# Sheet1.net
KiCad netlist of a schematic drawn in Altium Designer
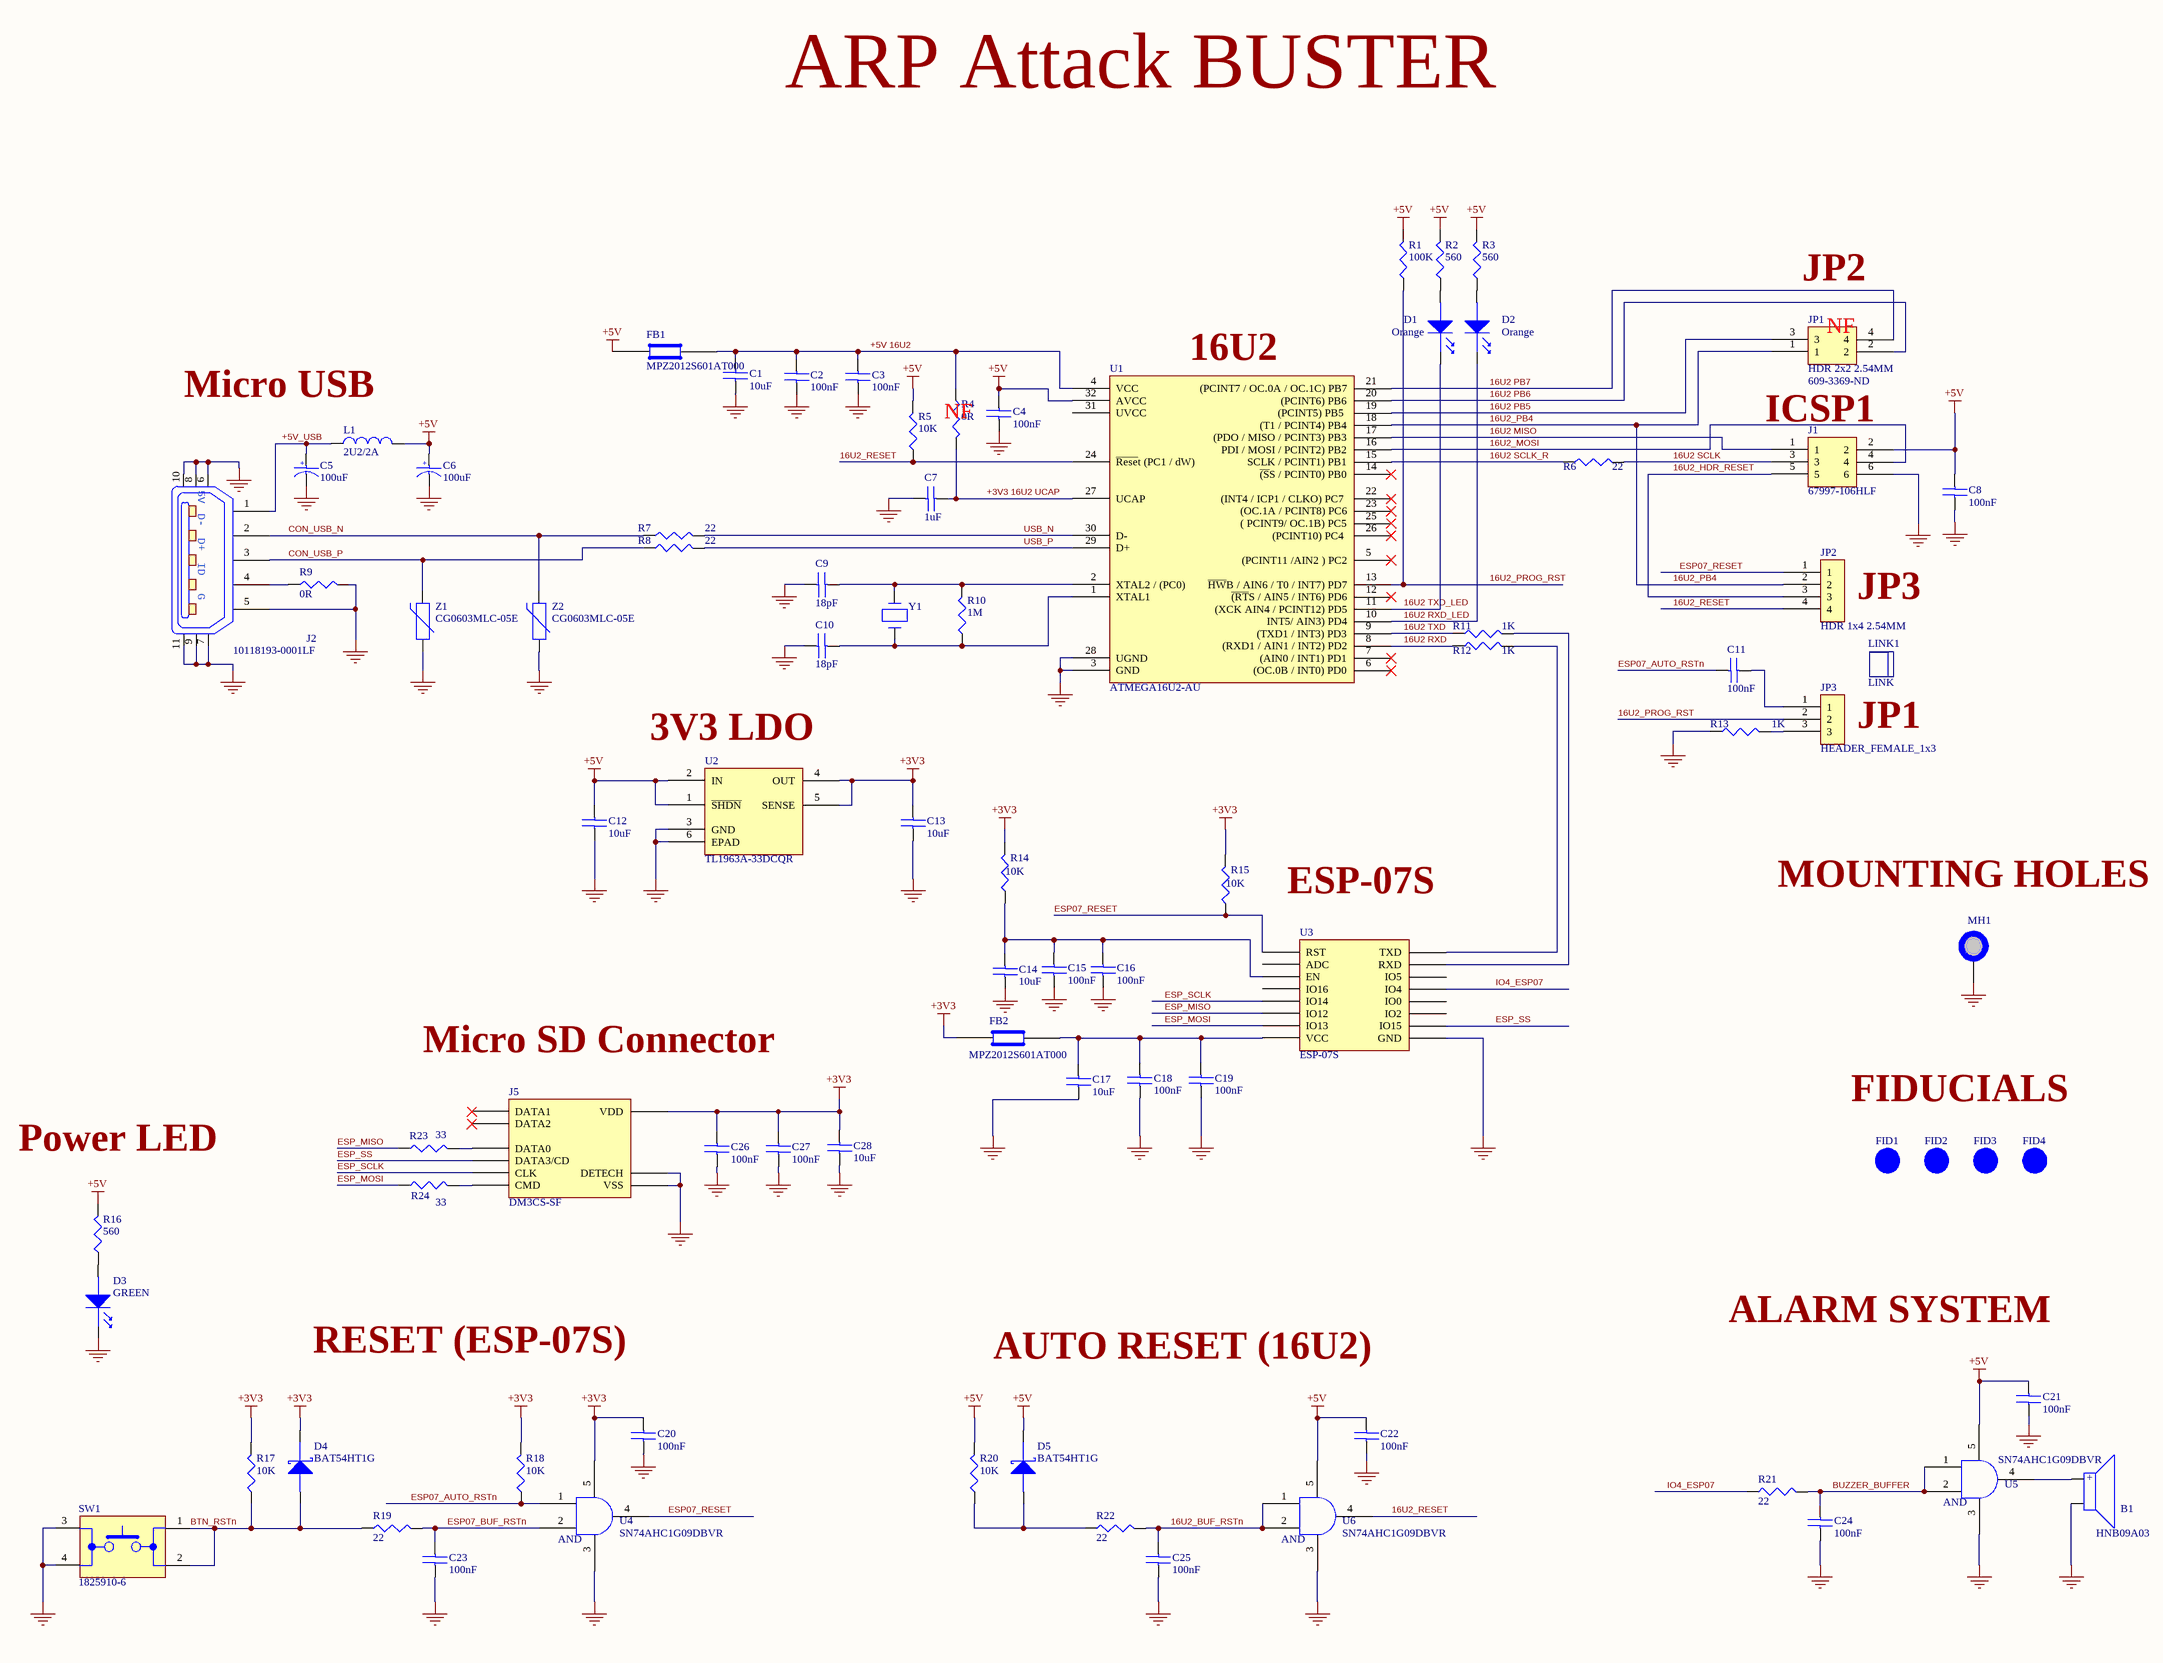
[diagram p0: Sheet1.SchDoc]

(export (version "E")
  (design (tool "Eeschema 10.0.6"))
  (components
    (comp (ref "B1")
      (value "HNB09A03")
      (footprint "Buzzer_HNB09A03")
      (description "Buzzer")
      (fields (field (name "MANUFACTURER") "Jiangsu Huaneng Elec"))
      (libsource (lib "schmaticSMDv1") (part "HNB09A03"))
    )
    (comp (ref "C1")
      (value "10uF")
      (footprint "C0805")
      (description "Cap Ceramic 10uF 10V X7S 20% Pad SMD 0805 125°C Low ESR Automotive T/R")
      (fields
        (field (name "MANUFACTURER") "TDK")
        (field (name "MANUFACTURER PART NUMBER") "CGA4J3X7S1A106M125AB")
      )
      (libsource (lib "atmega_shlib") (part "CGA4J3X7S1A106M125AB"))
    )
    (comp (ref "C2")
      (value "100nF")
      (footprint "C0805")
      (description "Cap Ceramic 0.1uF 50V X7R 10% Pad SMD 0805 125°C Automotive T/R")
      (fields
        (field (name "MANUFACTURER") "TDK")
        (field (name "MANUFACTURER PART NUMBER") "CGA4J2X7R1H104K125AM")
      )
      (libsource (lib "atmega_shlib") (part "CGA4J2X7R1H104K125AM"))
    )
    (comp (ref "C3")
      (value "100nF")
      (footprint "C0805")
      (description "Cap Ceramic 0.1uF 50V X7R 10% Pad SMD 0805 125°C Automotive T/R")
      (fields
        (field (name "MANUFACTURER") "TDK")
        (field (name "MANUFACTURER PART NUMBER") "CGA4J2X7R1H104K125AM")
      )
      (libsource (lib "atmega_shlib") (part "CGA4J2X7R1H104K125AM"))
    )
    (comp (ref "C4")
      (value "100nF")
      (footprint "C0805")
      (description "Cap Ceramic 0.1uF 50V X7R 10% Pad SMD 0805 125°C Automotive T/R")
      (fields
        (field (name "MANUFACTURER") "TDK")
        (field (name "MANUFACTURER PART NUMBER") "CGA4J2X7R1H104K125AM")
      )
      (libsource (lib "atmega_shlib") (part "CGA4J2X7R1H104K125AM"))
    )
    (comp (ref "C5")
      (value "100uF")
      (footprint "C_ALU_C_SIZE")
      (description "Cap Aluminum 100uF 10V 20% (5 X 5.4mm) SMD 50mA 1000 hr 85°C T/R")
      (fields
        (field (name "MANUFACTURER") "Panasonic")
        (field (name "MANUFACTURER PART NUMBER") "EEE-1AA101WR")
      )
      (libsource (lib "atmega_shlib") (part "EEE-1AA101WR"))
    )
    (comp (ref "C6")
      (value "100uF")
      (footprint "C_ALU_C_SIZE")
      (description "Cap Aluminum 100uF 10V 20% (5 X 5.4mm) SMD 50mA 1000 hr 85°C T/R")
      (fields
        (field (name "MANUFACTURER") "Panasonic")
        (field (name "MANUFACTURER PART NUMBER") "EEE-1AA101WR")
      )
      (libsource (lib "atmega_shlib") (part "EEE-1AA101WR"))
    )
    (comp (ref "C7")
      (value "1uF")
      (footprint "C0805")
      (fields
        (field (name "MANUFACTURER") "TDK")
        (field (name "MANUFACTURER PART NUMBER") "C2012X5R1E105K125AA")
        (field (name "TOLERANCE") "10%")
      )
      (libsource (lib "atmega_shlib") (part "C2012X5R1E105K125AA"))
    )
    (comp (ref "C8")
      (value "100nF")
      (footprint "C0805")
      (description "Cap Ceramic 0.1uF 50V X7R 10% Pad SMD 0805 125°C Automotive T/R")
      (fields
        (field (name "MANUFACTURER") "TDK")
        (field (name "MANUFACTURER PART NUMBER") "CGA4J2X7R1H104K125AM")
      )
      (libsource (lib "atmega_shlib") (part "CGA4J2X7R1H104K125AM"))
    )
    (comp (ref "C9")
      (value "18pF")
      (footprint "C0805")
      (description "Cap Ceramic 18pF 50V C0G 5% SMD 0805 125C Paper T/R")
      (fields
        (field (name "MANUFACTURER") "KEMET")
        (field (name "MANUFACTURER PART NUMBER") "C0805C180J5GACTU")
      )
      (libsource (lib "atmega_shlib") (part "C0805C180J5GACTU"))
    )
    (comp (ref "C10")
      (value "18pF")
      (footprint "C0805")
      (description "Cap Ceramic 18pF 50V C0G 5% SMD 0805 125C Paper T/R")
      (fields
        (field (name "MANUFACTURER") "KEMET")
        (field (name "MANUFACTURER PART NUMBER") "C0805C180J5GACTU")
      )
      (libsource (lib "atmega_shlib") (part "C0805C180J5GACTU"))
    )
    (comp (ref "C11")
      (value "100nF")
      (footprint "C0805")
      (description "Cap Ceramic 0.1uF 50V X7R 10% Pad SMD 0805 125°C Automotive T/R")
      (fields
        (field (name "MANUFACTURER") "TDK")
        (field (name "MANUFACTURER PART NUMBER") "CGA4J2X7R1H104K125AM")
      )
      (libsource (lib "atmega_shlib") (part "CGA4J2X7R1H104K125AM"))
    )
    (comp (ref "C12")
      (value "10uF")
      (footprint "C0805")
      (description "Cap Ceramic 10uF 10V X7S 20% Pad SMD 0805 125°C Low ESR Automotive T/R")
      (fields
        (field (name "MANUFACTURER") "TDK")
        (field (name "MANUFACTURER PART NUMBER") "CGA4J3X7S1A106M125AB")
      )
      (libsource (lib "atmega_shlib") (part "CGA4J3X7S1A106M125AB"))
    )
    (comp (ref "C13")
      (value "10uF")
      (footprint "C0805")
      (description "Cap Ceramic 10uF 10V X7S 20% Pad SMD 0805 125°C Low ESR Automotive T/R")
      (fields
        (field (name "MANUFACTURER") "TDK")
        (field (name "MANUFACTURER PART NUMBER") "CGA4J3X7S1A106M125AB")
      )
      (libsource (lib "atmega_shlib") (part "CGA4J3X7S1A106M125AB"))
    )
    (comp (ref "C14")
      (value "10uF")
      (footprint "C0805")
      (description "Cap Ceramic 10uF 10V X7S 20% Pad SMD 0805 125°C Low ESR Automotive T/R")
      (fields
        (field (name "MANUFACTURER") "TDK")
        (field (name "MANUFACTURER PART NUMBER") "CGA4J3X7S1A106M125AB")
      )
      (libsource (lib "schmaticSMDv1") (part "CGA4J3X7S1A106M125AB"))
    )
    (comp (ref "C15")
      (value "100nF")
      (footprint "C0805")
      (description "Cap Ceramic 0.1uF 50V X7R 10% Pad SMD 0805 125°C Automotive T/R")
      (fields
        (field (name "MANUFACTURER") "TDK")
        (field (name "MANUFACTURER PART NUMBER") "CGA4J2X7R1H104K125AM")
      )
      (libsource (lib "schmaticSMDv1") (part "CGA4J2X7R1H104K125AM"))
    )
    (comp (ref "C16")
      (value "100nF")
      (footprint "C0805")
      (description "Cap Ceramic 0.1uF 50V X7R 10% Pad SMD 0805 125°C Automotive T/R")
      (fields
        (field (name "MANUFACTURER") "TDK")
        (field (name "MANUFACTURER PART NUMBER") "CGA4J2X7R1H104K125AM")
      )
      (libsource (lib "schmaticSMDv1") (part "CGA4J2X7R1H104K125AM"))
    )
    (comp (ref "C17")
      (value "10uF")
      (footprint "C0805")
      (description "Cap Ceramic 10uF 10V X7S 20% Pad SMD 0805 125°C Low ESR Automotive T/R")
      (fields
        (field (name "MANUFACTURER") "TDK")
        (field (name "MANUFACTURER PART NUMBER") "CGA4J3X7S1A106M125AB")
      )
      (libsource (lib "schmaticSMDv1") (part "CGA4J3X7S1A106M125AB"))
    )
    (comp (ref "C18")
      (value "100nF")
      (footprint "C0805")
      (description "Cap Ceramic 0.1uF 50V X7R 10% Pad SMD 0805 125°C Automotive T/R")
      (fields
        (field (name "MANUFACTURER") "TDK")
        (field (name "MANUFACTURER PART NUMBER") "CGA4J2X7R1H104K125AM")
      )
      (libsource (lib "schmaticSMDv1") (part "CGA4J2X7R1H104K125AM"))
    )
    (comp (ref "C19")
      (value "100nF")
      (footprint "C0805")
      (description "Cap Ceramic 0.1uF 50V X7R 10% Pad SMD 0805 125°C Automotive T/R")
      (fields
        (field (name "MANUFACTURER") "TDK")
        (field (name "MANUFACTURER PART NUMBER") "CGA4J2X7R1H104K125AM")
      )
      (libsource (lib "schmaticSMDv1") (part "CGA4J2X7R1H104K125AM"))
    )
    (comp (ref "C20")
      (value "100nF")
      (footprint "C0805")
      (description "Cap Ceramic 0.1uF 50V X7R 10% Pad SMD 0805 125°C Automotive T/R")
      (fields
        (field (name "MANUFACTURER") "TDK")
        (field (name "MANUFACTURER PART NUMBER") "CGA4J2X7R1H104K125AM")
      )
      (libsource (lib "atmega_shlib") (part "CGA4J2X7R1H104K125AM"))
    )
    (comp (ref "C21")
      (value "100nF")
      (footprint "C0805")
      (description "Cap Ceramic 0.1uF 50V X7R 10% Pad SMD 0805 125°C Automotive T/R")
      (fields
        (field (name "MANUFACTURER") "TDK")
        (field (name "MANUFACTURER PART NUMBER") "CGA4J2X7R1H104K125AM")
      )
      (libsource (lib "atmega_shlib") (part "CGA4J2X7R1H104K125AM"))
    )
    (comp (ref "C22")
      (value "100nF")
      (footprint "C0805")
      (description "Cap Ceramic 0.1uF 50V X7R 10% Pad SMD 0805 125°C Automotive T/R")
      (fields
        (field (name "MANUFACTURER") "TDK")
        (field (name "MANUFACTURER PART NUMBER") "CGA4J2X7R1H104K125AM")
      )
      (libsource (lib "atmega_shlib") (part "CGA4J2X7R1H104K125AM"))
    )
    (comp (ref "C23")
      (value "100nF")
      (footprint "C0805")
      (description "Cap Ceramic 0.1uF 50V X7R 10% Pad SMD 0805 125°C Automotive T/R")
      (fields
        (field (name "MANUFACTURER") "TDK")
        (field (name "MANUFACTURER PART NUMBER") "CGA4J2X7R1H104K125AM")
      )
      (libsource (lib "atmega_shlib") (part "CGA4J2X7R1H104K125AM"))
    )
    (comp (ref "C24")
      (value "100nF")
      (footprint "C0805")
      (description "Cap Ceramic 0.1uF 50V X7R 10% Pad SMD 0805 125°C Automotive T/R")
      (fields
        (field (name "MANUFACTURER") "TDK")
        (field (name "MANUFACTURER PART NUMBER") "CGA4J2X7R1H104K125AM")
      )
      (libsource (lib "atmega_shlib") (part "CGA4J2X7R1H104K125AM"))
    )
    (comp (ref "C25")
      (value "100nF")
      (footprint "C0805")
      (description "Cap Ceramic 0.1uF 50V X7R 10% Pad SMD 0805 125°C Automotive T/R")
      (fields
        (field (name "MANUFACTURER") "TDK")
        (field (name "MANUFACTURER PART NUMBER") "CGA4J2X7R1H104K125AM")
      )
      (libsource (lib "atmega_shlib") (part "CGA4J2X7R1H104K125AM"))
    )
    (comp (ref "C26")
      (value "100nF")
      (footprint "C0805")
      (description "Cap Ceramic 0.1uF 50V X7R 10% Pad SMD 0805 125°C Automotive T/R")
      (fields
        (field (name "MANUFACTURER") "TDK")
        (field (name "MANUFACTURER PART NUMBER") "CGA4J2X7R1H104K125AM")
      )
      (libsource (lib "atmega_shlib") (part "CGA4J2X7R1H104K125AM"))
    )
    (comp (ref "C27")
      (value "100nF")
      (footprint "C0805")
      (description "Cap Ceramic 0.1uF 50V X7R 10% Pad SMD 0805 125°C Automotive T/R")
      (fields
        (field (name "MANUFACTURER") "TDK")
        (field (name "MANUFACTURER PART NUMBER") "CGA4J2X7R1H104K125AM")
      )
      (libsource (lib "atmega_shlib") (part "CGA4J2X7R1H104K125AM"))
    )
    (comp (ref "C28")
      (value "10uF")
      (footprint "C0805")
      (description "Cap Ceramic 10uF 10V X7S 20% Pad SMD 0805 125°C Low ESR Automotive T/R")
      (fields
        (field (name "MANUFACTURER") "TDK")
        (field (name "MANUFACTURER PART NUMBER") "CGA4J3X7S1A106M125AB")
      )
      (libsource (lib "atmega_shlib") (part "CGA4J3X7S1A106M125AB"))
    )
    (comp (ref "D1")
      (value "Orange")
      (footprint "LED0603")
      (description "Smartled Orange Lc")
      (fields
        (field (name "MANUFACTURER") "Osram Opto")
        (field (name "MANUFACTURER PART NUMBER") "LOL29K-H2K1-24-Z")
      )
      (libsource (lib "atmega_shlib") (part "LOL29K-H2K1-24-Z"))
    )
    (comp (ref "D2")
      (value "Orange")
      (footprint "LED0603")
      (description "Smartled Orange Lc")
      (fields
        (field (name "MANUFACTURER") "Osram Opto")
        (field (name "MANUFACTURER PART NUMBER") "LOL29K-H2K1-24-Z")
      )
      (libsource (lib "atmega_shlib") (part "LOL29K-H2K1-24-Z"))
    )
    (comp (ref "D3")
      (value "GREEN")
      (footprint "LED0603")
      (description "LED Single Chip Green 570nm 20mA 2-Pin 0603 T/R")
      (fields
        (field (name "MANUFACTURER") "Osram Opto")
        (field (name "MANUFACTURER PART NUMBER") "LGL29K-G2J1-24-Z")
      )
      (libsource (lib "atmega_shlib") (part "LGL29K-G2J1-24-Z"))
    )
    (comp (ref "D4")
      (value "BAT54HT1G")
      (footprint "SOD323")
      (description "Small Signal Schottky Diode, Single, 30 V, 200 Ma, 800 Mv, 600 Ma, 150 C")
      (fields (field (name "MANUFACTURER") "ON Semiconductor / Fairchild"))
      (libsource (lib "atmega_shlib") (part "BAT54HT1G"))
    )
    (comp (ref "D5")
      (value "BAT54HT1G")
      (footprint "SOD323")
      (description "Small Signal Schottky Diode, Single, 30 V, 200 Ma, 800 Mv, 600 Ma, 150 C")
      (fields (field (name "MANUFACTURER") "ON Semiconductor / Fairchild"))
      (libsource (lib "atmega_shlib") (part "BAT54HT1G"))
    )
    (comp (ref "FB1")
      (value "MPZ2012S601AT000")
      (footprint "C0805")
      (description "Ferrite Beads Multi-Layer Power 600Ohm 25% 100MHz 2A 100mOhm DCR 0805 T/R")
      (fields (field (name "MANUFACTURER") "TDK"))
      (libsource (lib "atmega_shlib") (part "MPZ2012S601AT000"))
    )
    (comp (ref "FB2")
      (value "MPZ2012S601AT000")
      (footprint "C0805")
      (description "Ferrite Beads Multi-Layer Power 600Ohm 25% 100MHz 2A 100mOhm DCR 0805 T/R")
      (fields (field (name "MANUFACTURER") "TDK"))
      (libsource (lib "atmega_shlib") (part "MPZ2012S601AT000"))
    )
    (comp (ref "FID1")
      (value "FID_1MM")
      (footprint "FID_x_420")
      (description "Fisushal 1MM")
      (libsource (lib "atmega_shlib") (part "FID_1MM"))
    )
    (comp (ref "FID2")
      (value "FID_1MM")
      (footprint "FID_x_420")
      (description "Fisushal 1MM")
      (libsource (lib "atmega_shlib") (part "FID_1MM"))
    )
    (comp (ref "FID3")
      (value "FID_1MM")
      (footprint "FID_x_420")
      (description "Fisushal 1MM")
      (libsource (lib "atmega_shlib") (part "FID_1MM"))
    )
    (comp (ref "FID4")
      (value "FID_1MM")
      (footprint "FID_x_420")
      (description "Fisushal 1MM")
      (libsource (lib "atmega_shlib") (part "FID_1MM"))
    )
    (comp (ref "J1")
      (value "67997-106HLF")
      (footprint "HDR_2x3_2.54MM")
      (description "Conn Unshrouded Header HDR 6 POS 2.54mm Solder ST Top Entry Thru-Hole BergStik® Bulk")
      (fields (field (name "MANUFACTURER") "ICC"))
      (libsource (lib "atmega_shlib") (part "67997-106HLF"))
    )
    (comp (ref "J2")
      (value "10118193-0001LF")
      (footprint "10118193-0001LF")
      (description "FCI Right Angle Surface Mount Mount Female USB Connector; 100 V ac; 1.8A")
      (fields (field (name "MANUFACTURER") "Amphenol ICC / FCI"))
      (libsource (lib "atmega_shlib") (part "10118193-0001LF"))
    )
    (comp (ref "J5")
      (value "DM3CS-SF")
      (footprint "GCT_MEM2051-00-195-00-A")
      (description "Connector, Memory, Micro Sd, Hinged Rohs Compliant: Yes")
      (fields (field (name "MANUFACTURER") "Hirose"))
      (libsource (lib "schmaticSMDv1") (part "DM3CS-SF"))
    )
    (comp (ref "JP1")
      (value "HDR 2x2 2.54MM")
      (footprint "HDR_2x2_2.54MM")
      (description "Conn Unshrouded Header HDR 4 POS 2.54mm Solder ST Top Entry Thru-Hole BergStik® Bulk")
      (fields
        (field (name "MANUFACTURER") "Amphenol ICC / FCI")
        (field (name "MANUFACTURER PART NUMBER") "68602-204HLF")
        (field (name "SUPPLIER PART NUMBER 1") "609-3369-ND")
      )
      (libsource (lib "atmega_shlib") (part "68602-204HLF"))
    )
    (comp (ref "JP2")
      (value "HDR 1x4 2.54MM")
      (footprint "MALEHEADER_1x4_2.54MM")
      (description "Conn Unshrouded Header HDR 4 POS 2.54mm Solder ST Thru-Hole Bag")
      (fields
        (field (name "MANUFACTURER") "Amphenol ICC / FCI")
        (field (name "MANUFACTURER PART NUMBER") "68001-204HLF")
      )
      (libsource (lib "atmega_shlib") (part "68001-204HLF"))
    )
    (comp (ref "JP3")
      (value "HEADER_FEMALE_1x3")
      (footprint "HDR_1x3_2.54MM")
      (description "Conn Unshrouded Header HDR 3 POS 2.54mm Solder ST Top Entry Thru-Hole BergStik® Automotive Bulk")
      (fields
        (field (name "MANUFACTURER") "Amphenol ICC")
        (field (name "MANUFACTURER PART NUMBER") "68000-103HLF")
      )
      (libsource (lib "atmega_shlib") (part "68000-103HLF"))
    )
    (comp (ref "L1")
      (value "2U2/2A")
      (footprint "CL_inductor")
      (description "Inductor RF Chip Wirewound 2.2uH 20% 100KHz 1.13A 0.104Ohm DCR 1210 T/R")
      (fields
        (field (name "MANUFACTURER") "KEMET")
        (field (name "MANUFACTURER PART NUMBER") "L1210R2R2MDWIT")
      )
      (libsource (lib "atmega_shlib") (part "L1210R2R2MDWIT"))
    )
    (comp (ref "LINK1")
      (value "LINK")
      (description "2 Position 2.54 mm Centerline Single Circuit Open Top Jumper")
      (fields
        (field (name "MANUFACTURER") "Sullins")
        (field (name "MANUFACTURER PART NUMBER") "QPC02SXGN-RC")
      )
      (libsource (lib "atmega_shlib") (part "QPC02SXGN-RC"))
    )
    (comp (ref "MH1")
      (value "Mounting_hole_17.4_3.2")
      (footprint "MH_17.4_3.2")
      (description "Mounting Hole plated")
      (libsource (lib "atmega_shlib") (part "Mounting_hole_17.4_3.2"))
    )
    (comp (ref "R1")
      (value "100K")
      (footprint "R0805")
      (description "Res Thick Film 0805 100K Ohm 1% 1/8W ±100ppm/°C Molded SMD Paper T/R")
      (fields
        (field (name "MANUFACTURER") "Yageo")
        (field (name "MANUFACTURER PART NUMBER") "RC0805FR-07100KL")
      )
      (libsource (lib "atmega_shlib") (part "RC0805FR-07100KL"))
    )
    (comp (ref "R2")
      (value "560")
      (footprint "R0805")
      (description "Res General Purpose Thick Film 0805 560 Ohm 1% 1/8W ±100ppm/°C Molded Paper T/R")
      (fields
        (field (name "MANUFACTURER") "Yageo")
        (field (name "MANUFACTURER PART NUMBER") "RC0805FR-07560RL")
      )
      (libsource (lib "atmega_shlib") (part "RC0805FR-07560RL"))
    )
    (comp (ref "R3")
      (value "560")
      (footprint "R0805")
      (description "Res General Purpose Thick Film 0805 560 Ohm 1% 1/8W ±100ppm/°C Molded Paper T/R")
      (fields
        (field (name "MANUFACTURER") "Yageo")
        (field (name "MANUFACTURER PART NUMBER") "RC0805FR-07560RL")
      )
      (libsource (lib "atmega_shlib") (part "RC0805FR-07560RL"))
    )
    (comp (ref "R4")
      (value "0R")
      (footprint "R0805")
      (description "RC Series 0805 0.125 W 0 Ohm Jumper Surface Mount Thick Film Chip Resistor")
      (fields
        (field (name "MANUFACTURER") "Yageo")
        (field (name "MANUFACTURER PART NUMBER") "RC0805JR-070RL")
      )
      (libsource (lib "atmega_shlib") (part "RC0805JR-070RL"))
    )
    (comp (ref "R5")
      (value "10K")
      (footprint "R0805")
      (description "Res SMD 0805 10K 1% 0.125W T.C.100PPM")
      (fields
        (field (name "MANUFACTURER") "Yageo")
        (field (name "MANUFACTURER PART NUMBER") "RC0805FR-0710KL")
      )
      (libsource (lib "atmega_shlib") (part "RC0805FR-0710KL"))
    )
    (comp (ref "R6")
      (value "22")
      (footprint "R0805")
      (description "Res SMD 0805 22R 1% 0.125W T.C.100PPM")
      (fields
        (field (name "MANUFACTURER") "Yageo")
        (field (name "MANUFACTURER PART NUMBER") "RC0805FR-0722RL")
      )
      (libsource (lib "atmega_shlib") (part "RC0805FR-0722RL"))
    )
    (comp (ref "R7")
      (value "22")
      (footprint "R0805")
      (description "Res SMD 0805 22R 1% 0.125W T.C.100PPM")
      (fields
        (field (name "MANUFACTURER") "Yageo")
        (field (name "MANUFACTURER PART NUMBER") "RC0805FR-0722RL")
      )
      (libsource (lib "atmega_shlib") (part "RC0805FR-0722RL"))
    )
    (comp (ref "R8")
      (value "22")
      (footprint "R0805")
      (description "Res SMD 0805 22R 1% 0.125W T.C.100PPM")
      (fields
        (field (name "MANUFACTURER") "Yageo")
        (field (name "MANUFACTURER PART NUMBER") "RC0805FR-0722RL")
      )
      (libsource (lib "atmega_shlib") (part "RC0805FR-0722RL"))
    )
    (comp (ref "R9")
      (value "0R")
      (footprint "R0805")
      (description "RC Series 0805 0.125 W 0 Ohm Jumper Surface Mount Thick Film Chip Resistor")
      (fields
        (field (name "MANUFACTURER") "Yageo")
        (field (name "MANUFACTURER PART NUMBER") "RC0805JR-070RL")
      )
      (libsource (lib "atmega_shlib") (part "RC0805JR-070RL"))
    )
    (comp (ref "R10")
      (value "1M")
      (footprint "R0805")
      (description "Res Thick Film 0805 1M Ohm 1% 0.125W(1/8W) ±100ppm/C Pad SMD T/R")
      (fields
        (field (name "MANUFACTURER") "Yageo Phycomp")
        (field (name "MANUFACTURER PART NUMBER") "RC0805FR-071ML")
      )
      (libsource (lib "atmega_shlib") (part "RC0805FR-071ML"))
    )
    (comp (ref "R11")
      (value "1K")
      (footprint "R0805")
      (description "Res Thick Film 0805 1KOhm 1% 0.125W(1/8W) 100ppm/C Epoxy Pad SMD T/R")
      (fields
        (field (name "MANUFACTURER") "Yageo")
        (field (name "MANUFACTURER PART NUMBER") "RC0805FR-071KL")
      )
      (libsource (lib "atmega_shlib") (part "RC0805FR-071KL"))
    )
    (comp (ref "R12")
      (value "1K")
      (footprint "R0805")
      (description "Res Thick Film 0805 1KOhm 1% 0.125W(1/8W) 100ppm/C Epoxy Pad SMD T/R")
      (fields
        (field (name "MANUFACTURER") "Yageo")
        (field (name "MANUFACTURER PART NUMBER") "RC0805FR-071KL")
      )
      (libsource (lib "atmega_shlib") (part "RC0805FR-071KL"))
    )
    (comp (ref "R13")
      (value "1K")
      (footprint "R0805")
      (description "Res Thick Film 0805 1KOhm 1% 0.125W(1/8W) 100ppm/C Epoxy Pad SMD T/R")
      (fields
        (field (name "MANUFACTURER") "Yageo")
        (field (name "MANUFACTURER PART NUMBER") "RC0805FR-071KL")
      )
      (libsource (lib "atmega_shlib") (part "RC0805FR-071KL"))
    )
    (comp (ref "R14")
      (value "10K")
      (footprint "R0805")
      (description "Res SMD 0805 10K 1% 0.125W T.C.100PPM")
      (fields
        (field (name "MANUFACTURER") "Yageo")
        (field (name "MANUFACTURER PART NUMBER") "RC0805FR-0710KL")
      )
      (libsource (lib "atmega_shlib") (part "RC0805FR-0710KL"))
    )
    (comp (ref "R15")
      (value "10K")
      (footprint "R0805")
      (description "Res SMD 0805 10K 1% 0.125W T.C.100PPM")
      (fields
        (field (name "MANUFACTURER") "Yageo")
        (field (name "MANUFACTURER PART NUMBER") "RC0805FR-0710KL")
      )
      (libsource (lib "atmega_shlib") (part "RC0805FR-0710KL"))
    )
    (comp (ref "R16")
      (value "560")
      (footprint "R0805")
      (description "Res General Purpose Thick Film 0805 560 Ohm 1% 1/8W ±100ppm/°C Molded Paper T/R")
      (fields
        (field (name "MANUFACTURER") "Yageo")
        (field (name "MANUFACTURER PART NUMBER") "RC0805FR-07560RL")
      )
      (libsource (lib "atmega_shlib") (part "RC0805FR-07560RL"))
    )
    (comp (ref "R17")
      (value "10K")
      (footprint "R0805")
      (description "Res SMD 0805 10K 1% 0.125W T.C.100PPM")
      (fields
        (field (name "MANUFACTURER") "Yageo")
        (field (name "MANUFACTURER PART NUMBER") "RC0805FR-0710KL")
      )
      (libsource (lib "atmega_shlib") (part "RC0805FR-0710KL"))
    )
    (comp (ref "R18")
      (value "10K")
      (footprint "R0805")
      (description "Res SMD 0805 10K 1% 0.125W T.C.100PPM")
      (fields
        (field (name "MANUFACTURER") "Yageo")
        (field (name "MANUFACTURER PART NUMBER") "RC0805FR-0710KL")
      )
      (libsource (lib "atmega_shlib") (part "RC0805FR-0710KL"))
    )
    (comp (ref "R19")
      (value "22")
      (footprint "R0805")
      (description "Res SMD 0805 22R 1% 0.125W T.C.100PPM")
      (fields
        (field (name "MANUFACTURER") "Yageo")
        (field (name "MANUFACTURER PART NUMBER") "RC0805FR-0722RL")
      )
      (libsource (lib "atmega_shlib") (part "RC0805FR-0722RL"))
    )
    (comp (ref "R20")
      (value "10K")
      (footprint "R0805")
      (description "Res SMD 0805 10K 1% 0.125W T.C.100PPM")
      (fields
        (field (name "MANUFACTURER") "Yageo")
        (field (name "MANUFACTURER PART NUMBER") "RC0805FR-0710KL")
      )
      (libsource (lib "atmega_shlib") (part "RC0805FR-0710KL"))
    )
    (comp (ref "R21")
      (value "22")
      (footprint "R0805")
      (description "Res SMD 0805 22R 1% 0.125W T.C.100PPM")
      (fields
        (field (name "MANUFACTURER") "Yageo")
        (field (name "MANUFACTURER PART NUMBER") "RC0805FR-0722RL")
      )
      (libsource (lib "atmega_shlib") (part "RC0805FR-0722RL"))
    )
    (comp (ref "R22")
      (value "22")
      (footprint "R0805")
      (description "Res SMD 0805 22R 1% 0.125W T.C.100PPM")
      (fields
        (field (name "MANUFACTURER") "Yageo")
        (field (name "MANUFACTURER PART NUMBER") "RC0805FR-0722RL")
      )
      (libsource (lib "atmega_shlib") (part "RC0805FR-0722RL"))
    )
    (comp (ref "R23")
      (value "33")
      (footprint "R0805")
      (description "Res Thick Film 2010 33 Ohm 1% 1W ±100ppm/C Pad SMD Automotive T/R")
      (fields
        (field (name "MANUFACTURER") "Stackpole Electronics")
        (field (name "MANUFACTURER PART NUMBER") "RMCP2010FT33R0")
      )
      (libsource (lib "schmaticSMDv1") (part "RMCP2010FT33R0"))
    )
    (comp (ref "R24")
      (value "33")
      (footprint "R0805")
      (description "Res Thick Film 2010 33 Ohm 1% 1W ±100ppm/C Pad SMD Automotive T/R")
      (fields
        (field (name "MANUFACTURER") "Stackpole Electronics")
        (field (name "MANUFACTURER PART NUMBER") "RMCP2010FT33R0")
      )
      (libsource (lib "schmaticSMDv1") (part "RMCP2010FT33R0"))
    )
    (comp (ref "SW1")
      (value "1825910-6")
      (footprint "DIP41825910-6")
      (description "Switch Tactile OFF (ON) SPST Round Button PC Pins 0.05A 24VDC 1.57N Thru-Hole Loose")
      (fields (field (name "MANUFACTURER") "TE Connectivity Alcoswitch"))
      (libsource (lib "atmega_shlib") (part "1825910-6"))
    )
    (comp (ref "U1")
      (value "ATMEGA16U2-AU")
      (footprint "TQFP_32")
      (description "8-bit AVR MCU, 16 KB, 512 Bytes, 16 MHz, 2.7 to 5.5V, TQFP-32, RoHS")
      (fields (field (name "MANUFACTURER") "Microchip / Atmel"))
      (libsource (lib "atmega_shlib") (part "ATMEGA16U2-AU"))
    )
    (comp (ref "U2")
      (value "TL1963A-33DCQR")
      (footprint "TL1963A-33DCQR")
      (description "LDO Regulator Pos 3.3V 1.5A 6-Pin(5+Tab) SOT-223 T/R")
      (fields (field (name "MANUFACTURER") "Texas Instruments"))
      (libsource (lib "atmega_shlib") (part "TL1963A-33DCQR"))
    )
    (comp (ref "U3")
      (value "ESP-07S")
      (footprint "ESP-07S")
      (description "Wifi Module, 2.484Ghz, 9 I/o Port Rohs Compliant: Yes")
      (fields
        (field (name "MANUFACTURER") "RF Solutions")
        (field (name "MANUFACTURER PART NUMBER") "ESP-12S")
      )
      (libsource (lib "schmaticSMDv1") (part "ESP-07S"))
    )
    (comp (ref "U4")
      (value "SN74AHC1G09DBVR")
      (footprint "DBV_SOT_5")
      (description "Single 2-input, 2-V to 5.5-V AND gate with open-drain outputs 5-SOT-23 -55 to 125")
      (fields (field (name "MANUFACTURER") "Texas Instruments"))
      (libsource (lib "atmega_shlib") (part "SN74AHC1G09DBVR"))
    )
    (comp (ref "U5")
      (value "SN74AHC1G09DBVR")
      (footprint "DBV_SOT_5")
      (description "Single 2-input, 2-V to 5.5-V AND gate with open-drain outputs 5-SOT-23 -55 to 125")
      (fields (field (name "MANUFACTURER") "Texas Instruments"))
      (libsource (lib "atmega_shlib") (part "SN74AHC1G09DBVR"))
    )
    (comp (ref "U6")
      (value "SN74AHC1G09DBVR")
      (footprint "DBV_SOT_5")
      (description "Single 2-input, 2-V to 5.5-V AND gate with open-drain outputs 5-SOT-23 -55 to 125")
      (fields (field (name "MANUFACTURER") "Texas Instruments"))
      (libsource (lib "atmega_shlib") (part "SN74AHC1G09DBVR"))
    )
    (comp (ref "Y1")
      (value "ABM7-16.000MHZ-D2Y-T")
      (footprint "ABM4_v1_1_BIG")
      (description "Crystal 16MHz ±20ppm (Tol) ±30ppm (Stability) 18pF FUND 50Ohm 2-Pin Mini-CSMD T/R")
      (fields (field (name "MANUFACTURER") "Abracon") (field (name "TOLERANCE") "20ppm"))
      (libsource (lib "atmega_shlib") (part "ABM7-16.000MHZ-D2Y-T"))
    )
    (comp (ref "Z1")
      (value "CG0603MLC-05E")
      (footprint "R0603")
      (description "ESD Suppressor Multilayer Varistor 5V Automotive 2-Pin Case 0603(1608Metric) T/R")
      (fields (field (name "MANUFACTURER") "Bourns") (field (name "VOLTAGE") "5V"))
      (libsource (lib "atmega_shlib") (part "CG0603MLC-05E"))
    )
    (comp (ref "Z2")
      (value "CG0603MLC-05E")
      (footprint "R0603")
      (description "ESD Suppressor Multilayer Varistor 5V Automotive 2-Pin Case 0603(1608Metric) T/R")
      (fields (field (name "MANUFACTURER") "Bourns") (field (name "VOLTAGE") "5V"))
      (libsource (lib "atmega_shlib") (part "CG0603MLC-05E"))
    )
  )
  (nets
    (net (code "1") (name "+3V3") (class "Default")
      (node (ref "C13") (pin "2") (pinfunction "2_2") (pintype "passive"))
      (node (ref "C20") (pin "2") (pinfunction "2_2") (pintype "passive"))
      (node (ref "C26") (pin "2") (pinfunction "2_2") (pintype "passive"))
      (node (ref "C27") (pin "2") (pinfunction "2_2") (pintype "passive"))
      (node (ref "C28") (pin "2") (pinfunction "2_2") (pintype "passive"))
      (node (ref "D4") (pin "1") (pinfunction "Ca_1") (pintype "passive"))
      (node (ref "FB2") (pin "1") (pinfunction "1_1") (pintype "passive"))
      (node (ref "J5") (pin "4") (pinfunction "VDD_4") (pintype "passive"))
      (node (ref "R14") (pin "2") (pinfunction "2_2") (pintype "passive"))
      (node (ref "R15") (pin "2") (pinfunction "2_2") (pintype "passive"))
      (node (ref "R17") (pin "2") (pinfunction "2_2") (pintype "passive"))
      (node (ref "R18") (pin "2") (pinfunction "2_2") (pintype "passive"))
      (node (ref "U2") (pin "4") (pinfunction "OUT_4") (pintype "passive"))
      (node (ref "U2") (pin "5") (pinfunction "SENSE_5") (pintype "passive"))
      (node (ref "U4") (pin "5") (pinfunction "5_5") (pintype "passive"))
    )
    (net (code "2") (name "+5V") (class "Default")
      (node (ref "C12") (pin "2") (pinfunction "2_2") (pintype "passive"))
      (node (ref "C21") (pin "2") (pinfunction "2_2") (pintype "passive"))
      (node (ref "C22") (pin "2") (pinfunction "2_2") (pintype "passive"))
      (node (ref "C4") (pin "2") (pinfunction "2_2") (pintype "passive"))
      (node (ref "C6") (pin "1") (pinfunction "1_1") (pintype "passive"))
      (node (ref "C8") (pin "2") (pinfunction "2_2") (pintype "passive"))
      (node (ref "D5") (pin "1") (pinfunction "Ca_1") (pintype "passive"))
      (node (ref "FB1") (pin "1") (pinfunction "1_1") (pintype "passive"))
      (node (ref "J1") (pin "2") (pinfunction "2_2") (pintype "passive"))
      (node (ref "L1") (pin "2") (pinfunction "2_2") (pintype "passive"))
      (node (ref "R1") (pin "2") (pinfunction "2_2") (pintype "passive"))
      (node (ref "R16") (pin "2") (pinfunction "2_2") (pintype "passive"))
      (node (ref "R2") (pin "2") (pinfunction "2_2") (pintype "passive"))
      (node (ref "R20") (pin "2") (pinfunction "2_2") (pintype "passive"))
      (node (ref "R3") (pin "2") (pinfunction "2_2") (pintype "passive"))
      (node (ref "R5") (pin "2") (pinfunction "2_2") (pintype "passive"))
      (node (ref "U1") (pin "32") (pinfunction "AVCC_32") (pintype "passive"))
      (node (ref "U2") (pin "1") (pinfunction "~{SHDN}_1") (pintype "passive"))
      (node (ref "U2") (pin "2") (pinfunction "IN_2") (pintype "passive"))
      (node (ref "U5") (pin "5") (pinfunction "5_5") (pintype "passive"))
      (node (ref "U6") (pin "5") (pinfunction "5_5") (pintype "passive"))
    )
    (net (code "3") (name "/+3V3 16U2 UCAP") (class "Default")
      (node (ref "C7") (pin "2") (pinfunction "2_2") (pintype "passive"))
      (node (ref "R4") (pin "2") (pinfunction "2_2") (pintype "passive"))
      (node (ref "U1") (pin "27") (pinfunction "UCAP_27") (pintype "passive"))
    )
    (net (code "4") (name "/+5V 16U2") (class "Default")
      (node (ref "C1") (pin "2") (pinfunction "2_2") (pintype "passive"))
      (node (ref "C2") (pin "2") (pinfunction "2_2") (pintype "passive"))
      (node (ref "C3") (pin "2") (pinfunction "2_2") (pintype "passive"))
      (node (ref "FB1") (pin "2") (pinfunction "2_2") (pintype "passive"))
      (node (ref "R4") (pin "1") (pinfunction "1_1") (pintype "passive"))
      (node (ref "U1") (pin "4") (pinfunction "VCC_4") (pintype "passive"))
    )
    (net (code "5") (name "/+5V_USB") (class "Default")
      (node (ref "C5") (pin "1") (pinfunction "1_1") (pintype "passive"))
      (node (ref "J2") (pin "1") (pinfunction "1_1") (pintype "passive"))
      (node (ref "L1") (pin "1") (pinfunction "1_1") (pintype "passive"))
    )
    (net (code "6") (name "/16U2 MISO") (class "Default")
      (node (ref "J1") (pin "1") (pinfunction "1_1") (pintype "passive"))
      (node (ref "U1") (pin "17") (pinfunction "(PDO_/_MISO_/_PCINT3)_PB3_17") (pintype "passive"))
    )
    (net (code "7") (name "/16U2 PB5") (class "Default")
      (node (ref "JP1") (pin "3") (pinfunction "3_3") (pintype "passive"))
      (node (ref "U1") (pin "19") (pinfunction "(PCINT5)_PB5_19") (pintype "passive"))
    )
    (net (code "8") (name "/16U2 PB6") (class "Default")
      (node (ref "JP1") (pin "2") (pinfunction "2_2") (pintype "passive"))
      (node (ref "U1") (pin "20") (pinfunction "(PCINT6)_PB6_20") (pintype "passive"))
    )
    (net (code "9") (name "/16U2 PB7") (class "Default")
      (node (ref "JP1") (pin "4") (pinfunction "4_4") (pintype "passive"))
      (node (ref "U1") (pin "21") (pinfunction "(PCINT7_/_OC.0A_/_OC.1C)_PB7_21") (pintype "passive"))
    )
    (net (code "10") (name "/16U2 RXD") (class "Default")
      (node (ref "R12") (pin "1") (pinfunction "1_1") (pintype "passive"))
      (node (ref "U1") (pin "8") (pinfunction "(RXD1_/_AIN1_/_INT2)_PD2_8") (pintype "passive"))
    )
    (net (code "11") (name "/16U2 RXD_LED") (class "Default")
      (node (ref "D2") (pin "1") (pinfunction "Ca_1") (pintype "passive"))
      (node (ref "U1") (pin "10") (pinfunction "INT5/_AIN3)_PD4_10") (pintype "passive"))
    )
    (net (code "12") (name "/16U2 SCLK") (class "Default")
      (node (ref "J1") (pin "3") (pinfunction "3_3") (pintype "passive"))
      (node (ref "R6") (pin "2") (pinfunction "2_2") (pintype "passive"))
    )
    (net (code "13") (name "/16U2 SCLK_R") (class "Default")
      (node (ref "R6") (pin "1") (pinfunction "1_1") (pintype "passive"))
      (node (ref "U1") (pin "15") (pinfunction "SCLK_/_PCINT1)_PB1_15") (pintype "passive"))
    )
    (net (code "14") (name "/16U2 TXD") (class "Default")
      (node (ref "R11") (pin "1") (pinfunction "1_1") (pintype "passive"))
      (node (ref "U1") (pin "9") (pinfunction "(TXD1_/_INT3)_PD3_9") (pintype "passive"))
    )
    (net (code "15") (name "/16U2 TXD_LED") (class "Default")
      (node (ref "D1") (pin "1") (pinfunction "Ca_1") (pintype "passive"))
      (node (ref "U1") (pin "11") (pinfunction "(XCK_AIN4_/_PCINT12)_PD5_11") (pintype "passive"))
    )
    (net (code "16") (name "/16U2_BUF_RSTn") (class "Default")
      (node (ref "C25") (pin "2") (pinfunction "2_2") (pintype "passive"))
      (node (ref "R22") (pin "2") (pinfunction "2_2") (pintype "passive"))
      (node (ref "U6") (pin "1") (pinfunction "1_1") (pintype "passive"))
      (node (ref "U6") (pin "2") (pinfunction "2_2") (pintype "passive"))
    )
    (net (code "17") (name "/16U2_HDR_RESET") (class "Default")
      (node (ref "J1") (pin "5") (pinfunction "5_5") (pintype "passive"))
      (node (ref "JP2") (pin "3") (pinfunction "3_3") (pintype "passive"))
    )
    (net (code "18") (name "/16U2_MOSI") (class "Default")
      (node (ref "J1") (pin "4") (pinfunction "4_4") (pintype "passive"))
      (node (ref "U1") (pin "16") (pinfunction "PDI_/_MOSI_/_PCINT2)_PB2_16") (pintype "passive"))
    )
    (net (code "19") (name "/16U2_PB4") (class "Default")
      (node (ref "JP1") (pin "1") (pinfunction "1_1") (pintype "passive"))
      (node (ref "JP2") (pin "2") (pinfunction "2_2") (pintype "passive"))
      (node (ref "U1") (pin "18") (pinfunction "(T1_/_PCINT4)_PB4_18") (pintype "passive"))
    )
    (net (code "20") (name "/16U2_PROG_RST") (class "Default")
      (node (ref "JP3") (pin "2") (pinfunction "2_2") (pintype "passive"))
      (node (ref "R1") (pin "1") (pinfunction "1_1") (pintype "passive"))
      (node (ref "U1") (pin "13") (pinfunction "~{HW}B_/_AIN6_/_T0_/_INT7)_PD7_13") (pintype "passive"))
    )
    (net (code "21") (name "/16U2_RESET") (class "Default")
      (node (ref "JP2") (pin "4") (pinfunction "4_4") (pintype "passive"))
      (node (ref "R5") (pin "1") (pinfunction "1_1") (pintype "passive"))
      (node (ref "U1") (pin "24") (pinfunction "~{Rese}t_(PC1_/_dW)_24") (pintype "passive"))
      (node (ref "U6") (pin "4") (pinfunction "4_4") (pintype "passive"))
    )
    (net (code "22") (name "/BTN_RSTn") (class "Default")
      (node (ref "D4") (pin "2") (pinfunction "An_2") (pintype "passive"))
      (node (ref "R17") (pin "1") (pinfunction "1_1") (pintype "passive"))
      (node (ref "R19") (pin "1") (pinfunction "1_1") (pintype "passive"))
      (node (ref "SW1") (pin "1") (pinfunction "1_1") (pintype "passive"))
      (node (ref "SW1") (pin "2") (pinfunction "2_2") (pintype "passive"))
    )
    (net (code "23") (name "/BUZZER_BUFFER") (class "Default")
      (node (ref "C24") (pin "2") (pinfunction "2_2") (pintype "passive"))
      (node (ref "R21") (pin "2") (pinfunction "2_2") (pintype "passive"))
      (node (ref "U5") (pin "1") (pinfunction "1_1") (pintype "passive"))
      (node (ref "U5") (pin "2") (pinfunction "2_2") (pintype "passive"))
    )
    (net (code "24") (name "/CON_USB_N") (class "Default")
      (node (ref "J2") (pin "2") (pinfunction "2_2") (pintype "passive"))
      (node (ref "R7") (pin "1") (pinfunction "1_1") (pintype "passive"))
      (node (ref "Z2") (pin "2") (pinfunction "2_2") (pintype "passive"))
    )
    (net (code "25") (name "/CON_USB_P") (class "Default")
      (node (ref "J2") (pin "3") (pinfunction "3_3") (pintype "passive"))
      (node (ref "R8") (pin "1") (pinfunction "1_1") (pintype "passive"))
      (node (ref "Z1") (pin "2") (pinfunction "2_2") (pintype "passive"))
    )
    (net (code "26") (name "/ESP07_AUTO_RSTn") (class "Default")
      (node (ref "C11") (pin "1") (pinfunction "1_1") (pintype "passive"))
      (node (ref "R18") (pin "1") (pinfunction "1_1") (pintype "passive"))
      (node (ref "U4") (pin "1") (pinfunction "1_1") (pintype "passive"))
    )
    (net (code "27") (name "/ESP07_BUF_RSTn") (class "Default")
      (node (ref "C23") (pin "2") (pinfunction "2_2") (pintype "passive"))
      (node (ref "R19") (pin "2") (pinfunction "2_2") (pintype "passive"))
      (node (ref "U4") (pin "2") (pinfunction "2_2") (pintype "passive"))
    )
    (net (code "28") (name "/ESP07_RESET") (class "Default")
      (node (ref "JP2") (pin "1") (pinfunction "1_1") (pintype "passive"))
      (node (ref "R15") (pin "1") (pinfunction "1_1") (pintype "passive"))
      (node (ref "U3") (pin "1") (pinfunction "RST_1") (pintype "passive"))
      (node (ref "U4") (pin "4") (pinfunction "4_4") (pintype "passive"))
    )
    (net (code "29") (name "/ESP_MISO") (class "Default")
      (node (ref "R23") (pin "1") (pinfunction "1_1") (pintype "passive"))
      (node (ref "U3") (pin "6") (pinfunction "IO12_6") (pintype "passive"))
    )
    (net (code "30") (name "/ESP_MOSI") (class "Default")
      (node (ref "R24") (pin "1") (pinfunction "1_1") (pintype "passive"))
      (node (ref "U3") (pin "7") (pinfunction "IO13_7") (pintype "passive"))
    )
    (net (code "31") (name "/ESP_SCLK") (class "Default")
      (node (ref "J5") (pin "5") (pinfunction "CLK_5") (pintype "passive"))
      (node (ref "U3") (pin "5") (pinfunction "IO14_5") (pintype "passive"))
    )
    (net (code "32") (name "/ESP_SS") (class "Default")
      (node (ref "J5") (pin "2") (pinfunction "DATA3/CD_2") (pintype "passive"))
      (node (ref "U3") (pin "10") (pinfunction "IO15_10") (pintype "passive"))
    )
    (net (code "33") (name "/IO4_ESP07") (class "Default")
      (node (ref "R21") (pin "1") (pinfunction "1_1") (pintype "passive"))
      (node (ref "U3") (pin "13") (pinfunction "IO4_13") (pintype "passive"))
    )
    (net (code "34") (name "/USB_N") (class "Default")
      (node (ref "R7") (pin "2") (pinfunction "2_2") (pintype "passive"))
      (node (ref "U1") (pin "30") (pinfunction "D-_30") (pintype "passive"))
    )
    (net (code "35") (name "/USB_P") (class "Default")
      (node (ref "R8") (pin "2") (pinfunction "2_2") (pintype "passive"))
      (node (ref "U1") (pin "29") (pinfunction "D+_29") (pintype "passive"))
    )
    (net (code "36") (name "GND") (class "Default")
      (node (ref "B1") (pin "1") (pinfunction "_1_1") (pintype "passive"))
      (node (ref "C1") (pin "1") (pinfunction "1_1") (pintype "passive"))
      (node (ref "C10") (pin "1") (pinfunction "1_1") (pintype "passive"))
      (node (ref "C12") (pin "1") (pinfunction "1_1") (pintype "passive"))
      (node (ref "C13") (pin "1") (pinfunction "1_1") (pintype "passive"))
      (node (ref "C14") (pin "1") (pinfunction "1_1") (pintype "passive"))
      (node (ref "C15") (pin "1") (pinfunction "1_1") (pintype "passive"))
      (node (ref "C16") (pin "1") (pinfunction "1_1") (pintype "passive"))
      (node (ref "C17") (pin "1") (pinfunction "1_1") (pintype "passive"))
      (node (ref "C18") (pin "1") (pinfunction "1_1") (pintype "passive"))
      (node (ref "C19") (pin "1") (pinfunction "1_1") (pintype "passive"))
      (node (ref "C2") (pin "1") (pinfunction "1_1") (pintype "passive"))
      (node (ref "C20") (pin "1") (pinfunction "1_1") (pintype "passive"))
      (node (ref "C21") (pin "1") (pinfunction "1_1") (pintype "passive"))
      (node (ref "C22") (pin "1") (pinfunction "1_1") (pintype "passive"))
      (node (ref "C23") (pin "1") (pinfunction "1_1") (pintype "passive"))
      (node (ref "C24") (pin "1") (pinfunction "1_1") (pintype "passive"))
      (node (ref "C25") (pin "1") (pinfunction "1_1") (pintype "passive"))
      (node (ref "C26") (pin "1") (pinfunction "1_1") (pintype "passive"))
      (node (ref "C27") (pin "1") (pinfunction "1_1") (pintype "passive"))
      (node (ref "C28") (pin "1") (pinfunction "1_1") (pintype "passive"))
      (node (ref "C3") (pin "1") (pinfunction "1_1") (pintype "passive"))
      (node (ref "C4") (pin "1") (pinfunction "1_1") (pintype "passive"))
      (node (ref "C5") (pin "2") (pinfunction "2_2") (pintype "passive"))
      (node (ref "C6") (pin "2") (pinfunction "2_2") (pintype "passive"))
      (node (ref "C7") (pin "1") (pinfunction "1_1") (pintype "passive"))
      (node (ref "C8") (pin "1") (pinfunction "1_1") (pintype "passive"))
      (node (ref "C9") (pin "1") (pinfunction "1_1") (pintype "passive"))
      (node (ref "D3") (pin "1") (pinfunction "Ca_1") (pintype "passive"))
      (node (ref "J1") (pin "6") (pinfunction "6_6") (pintype "passive"))
      (node (ref "J2") (pin "10") (pinfunction "10_10") (pintype "passive"))
      (node (ref "J2") (pin "11") (pinfunction "11_11") (pintype "passive"))
      (node (ref "J2") (pin "5") (pinfunction "5_5") (pintype "passive"))
      (node (ref "J2") (pin "6") (pinfunction "6_6") (pintype "passive"))
      (node (ref "J2") (pin "7") (pinfunction "7_7") (pintype "passive"))
      (node (ref "J2") (pin "8") (pinfunction "8_8") (pintype "passive"))
      (node (ref "J2") (pin "9") (pinfunction "9_9") (pintype "passive"))
      (node (ref "J5") (pin "6") (pinfunction "VSS_6") (pintype "passive"))
      (node (ref "J5") (pin "9") (pinfunction "DETECH_9") (pintype "passive"))
      (node (ref "MH1") (pin "1") (pinfunction "1_1") (pintype "passive"))
      (node (ref "R13") (pin "1") (pinfunction "1_1") (pintype "passive"))
      (node (ref "R9") (pin "2") (pinfunction "2_2") (pintype "passive"))
      (node (ref "SW1") (pin "3") (pinfunction "3_3") (pintype "passive"))
      (node (ref "SW1") (pin "4") (pinfunction "4_4") (pintype "passive"))
      (node (ref "U1") (pin "28") (pinfunction "UGND_28") (pintype "passive"))
      (node (ref "U1") (pin "3") (pinfunction "GND_3") (pintype "passive"))
      (node (ref "U2") (pin "3") (pinfunction "GND_3") (pintype "passive"))
      (node (ref "U2") (pin "6") (pinfunction "EPAD_6") (pintype "passive"))
      (node (ref "U3") (pin "9") (pinfunction "GND_9") (pintype "passive"))
      (node (ref "U4") (pin "3") (pinfunction "3_3") (pintype "passive"))
      (node (ref "U5") (pin "3") (pinfunction "3_3") (pintype "passive"))
      (node (ref "U6") (pin "3") (pinfunction "3_3") (pintype "passive"))
      (node (ref "Z1") (pin "1") (pinfunction "1_1") (pintype "passive"))
      (node (ref "Z2") (pin "1") (pinfunction "1_1") (pintype "passive"))
    )
    (net (code "37") (name "Net-(B1-Pad2)") (class "Default")
      (node (ref "B1") (pin "2") (pinfunction "2_2") (pintype "passive"))
      (node (ref "U5") (pin "4") (pinfunction "4_4") (pintype "passive"))
    )
    (net (code "38") (name "Net-(C11-Pad2)") (class "Default")
      (node (ref "C11") (pin "2") (pinfunction "2_2") (pintype "passive"))
      (node (ref "JP3") (pin "1") (pinfunction "1_1") (pintype "passive"))
    )
    (net (code "39") (name "Net-(D1-An)") (class "Default")
      (node (ref "D1") (pin "2") (pinfunction "An_2") (pintype "passive"))
      (node (ref "R2") (pin "1") (pinfunction "1_1") (pintype "passive"))
    )
    (net (code "40") (name "Net-(D2-An)") (class "Default")
      (node (ref "D2") (pin "2") (pinfunction "An_2") (pintype "passive"))
      (node (ref "R3") (pin "1") (pinfunction "1_1") (pintype "passive"))
    )
    (net (code "41") (name "Net-(D3-An)") (class "Default")
      (node (ref "D3") (pin "2") (pinfunction "An_2") (pintype "passive"))
      (node (ref "R16") (pin "1") (pinfunction "1_1") (pintype "passive"))
    )
    (net (code "42") (name "Net-(D5-An)") (class "Default")
      (node (ref "D5") (pin "2") (pinfunction "An_2") (pintype "passive"))
      (node (ref "R20") (pin "1") (pinfunction "1_1") (pintype "passive"))
      (node (ref "R22") (pin "1") (pinfunction "1_1") (pintype "passive"))
    )
    (net (code "43") (name "Net-(J2-Pad4)") (class "Default")
      (node (ref "J2") (pin "4") (pinfunction "4_4") (pintype "passive"))
      (node (ref "R9") (pin "1") (pinfunction "1_1") (pintype "passive"))
    )
    (net (code "44") (name "Net-(J5-CMD)") (class "Default")
      (node (ref "J5") (pin "3") (pinfunction "CMD_3") (pintype "passive"))
      (node (ref "R24") (pin "2") (pinfunction "2_2") (pintype "passive"))
    )
    (net (code "45") (name "Net-(J5-DATA0)") (class "Default")
      (node (ref "J5") (pin "7") (pinfunction "DATA0_7") (pintype "passive"))
      (node (ref "R23") (pin "2") (pinfunction "2_2") (pintype "passive"))
    )
    (net (code "46") (name "Net-(JP3-Pad3)") (class "Default")
      (node (ref "JP3") (pin "3") (pinfunction "3_3") (pintype "passive"))
      (node (ref "R13") (pin "2") (pinfunction "2_2") (pintype "passive"))
    )
    (net (code "47") (name "Net-(U1-XTAL1)") (class "Default")
      (node (ref "C10") (pin "2") (pinfunction "2_2") (pintype "passive"))
      (node (ref "R10") (pin "1") (pinfunction "1_1") (pintype "passive"))
      (node (ref "U1") (pin "1") (pinfunction "XTAL1_1") (pintype "passive"))
      (node (ref "Y1") (pin "1") (pinfunction "1_1") (pintype "passive"))
    )
    (net (code "48") (name "Net-(U1-XTAL2_{slash}_(PC0))") (class "Default")
      (node (ref "C9") (pin "2") (pinfunction "2_2") (pintype "passive"))
      (node (ref "R10") (pin "2") (pinfunction "2_2") (pintype "passive"))
      (node (ref "U1") (pin "2") (pinfunction "XTAL2_/_(PC0)_2") (pintype "passive"))
      (node (ref "Y1") (pin "2") (pinfunction "2_2") (pintype "passive"))
    )
    (net (code "49") (name "Net-(U3-EN)") (class "Default")
      (node (ref "C14") (pin "2") (pinfunction "2_2") (pintype "passive"))
      (node (ref "C15") (pin "2") (pinfunction "2_2") (pintype "passive"))
      (node (ref "C16") (pin "2") (pinfunction "2_2") (pintype "passive"))
      (node (ref "R14") (pin "1") (pinfunction "1_1") (pintype "passive"))
      (node (ref "U3") (pin "3") (pinfunction "EN_3") (pintype "passive"))
    )
    (net (code "50") (name "Net-(U3-RXD)") (class "Default")
      (node (ref "R11") (pin "2") (pinfunction "2_2") (pintype "passive"))
      (node (ref "U3") (pin "15") (pinfunction "RXD_15") (pintype "passive"))
    )
    (net (code "51") (name "Net-(U3-TXD)") (class "Default")
      (node (ref "R12") (pin "2") (pinfunction "2_2") (pintype "passive"))
      (node (ref "U3") (pin "16") (pinfunction "TXD_16") (pintype "passive"))
    )
    (net (code "52") (name "Net-(U3-VCC)") (class "Default")
      (node (ref "C17") (pin "2") (pinfunction "2_2") (pintype "passive"))
      (node (ref "C18") (pin "2") (pinfunction "2_2") (pintype "passive"))
      (node (ref "C19") (pin "2") (pinfunction "2_2") (pintype "passive"))
      (node (ref "FB2") (pin "2") (pinfunction "2_2") (pintype "passive"))
      (node (ref "U3") (pin "8") (pinfunction "VCC_8") (pintype "passive"))
    )
    (net (code "53") (name "unconnected-(J5-DATA1-Pad8)") (class "Default")
      (node (ref "J5") (pin "8") (pinfunction "DATA1_8") (pintype "passive+no_connect"))
    )
    (net (code "54") (name "unconnected-(J5-DATA2-Pad1)") (class "Default")
      (node (ref "J5") (pin "1") (pinfunction "DATA2_1") (pintype "passive+no_connect"))
    )
    (net (code "55") (name "unconnected-(U1-(AIN0_{slash}_INT1)_PD1-Pad7)") (class "Default")
      (node (ref "U1") (pin "7") (pinfunction "(AIN0_/_INT1)_PD1_7") (pintype "passive+no_connect"))
    )
    (net (code "56") (name "unconnected-(U1-(INT4_{slash}_ICP1_{slash}_CLKO)_PC7-Pad22)") (class "Default")
      (node (ref "U1") (pin "22") (pinfunction "(INT4_/_ICP1_/_CLKO)_PC7_22") (pintype "passive+no_connect"))
    )
    (net (code "57") (name "unconnected-(U1-(OC.0B_{slash}_INT0)_PD0-Pad6)") (class "Default")
      (node (ref "U1") (pin "6") (pinfunction "(OC.0B_/_INT0)_PD0_6") (pintype "passive+no_connect"))
    )
    (net (code "58") (name "unconnected-(U1-(OC.1A_{slash}_PCINT8)_PC6-Pad23)") (class "Default")
      (node (ref "U1") (pin "23") (pinfunction "(OC.1A_/_PCINT8)_PC6_23") (pintype "passive+no_connect"))
    )
    (net (code "59") (name "unconnected-(U1-(PCINT10)_PC4-Pad26)") (class "Default")
      (node (ref "U1") (pin "26") (pinfunction "(PCINT10)_PC4_26") (pintype "passive+no_connect"))
    )
    (net (code "60") (name "unconnected-(U1-(PCINT11_{slash}AIN2_)_PC2-Pad5)") (class "Default")
      (node (ref "U1") (pin "5") (pinfunction "(PCINT11_/AIN2_)_PC2_5") (pintype "passive+no_connect"))
    )
    (net (code "61") (name "unconnected-(U1-UVCC-Pad31)") (class "Default")
      (node (ref "U1") (pin "31") (pinfunction "UVCC_31") (pintype "passive"))
    )
    (net (code "62") (name "unconnected-(U1-_(_PCINT9{slash}_OC.1B)_PC5-Pad25)") (class "Default")
      (node (ref "U1") (pin "25") (pinfunction "_(_PCINT9/_OC.1B)_PC5_25") (pintype "passive+no_connect"))
    )
    (net (code "63") (name "unconnected-(U1-~{(RT}S_{slash}_AIN5_{slash}_INT6)_PD6-Pad12)") (class "Default")
      (node (ref "U1") (pin "12") (pinfunction "~{(RT}S_/_AIN5_/_INT6)_PD6_12") (pintype "passive+no_connect"))
    )
    (net (code "64") (name "unconnected-(U1-~{(S}S_{slash}_PCINT0)_PB0-Pad14)") (class "Default")
      (node (ref "U1") (pin "14") (pinfunction "~{(S}S_/_PCINT0)_PB0_14") (pintype "passive+no_connect"))
    )
    (net (code "65") (name "unconnected-(U3-ADC-Pad2)") (class "Default")
      (node (ref "U3") (pin "2") (pinfunction "ADC_2") (pintype "passive"))
    )
    (net (code "66") (name "unconnected-(U3-IO0-Pad12)") (class "Default")
      (node (ref "U3") (pin "12") (pinfunction "IO0_12") (pintype "passive"))
    )
    (net (code "67") (name "unconnected-(U3-IO2-Pad11)") (class "Default")
      (node (ref "U3") (pin "11") (pinfunction "IO2_11") (pintype "passive"))
    )
    (net (code "68") (name "unconnected-(U3-IO5-Pad14)") (class "Default")
      (node (ref "U3") (pin "14") (pinfunction "IO5_14") (pintype "passive"))
    )
    (net (code "69") (name "unconnected-(U3-IO16-Pad4)") (class "Default")
      (node (ref "U3") (pin "4") (pinfunction "IO16_4") (pintype "passive"))
    )
  )
)
